# 13_RK3568_FlashSD_Controller.net
KiCad netlist of a schematic drawn in Altium Designer
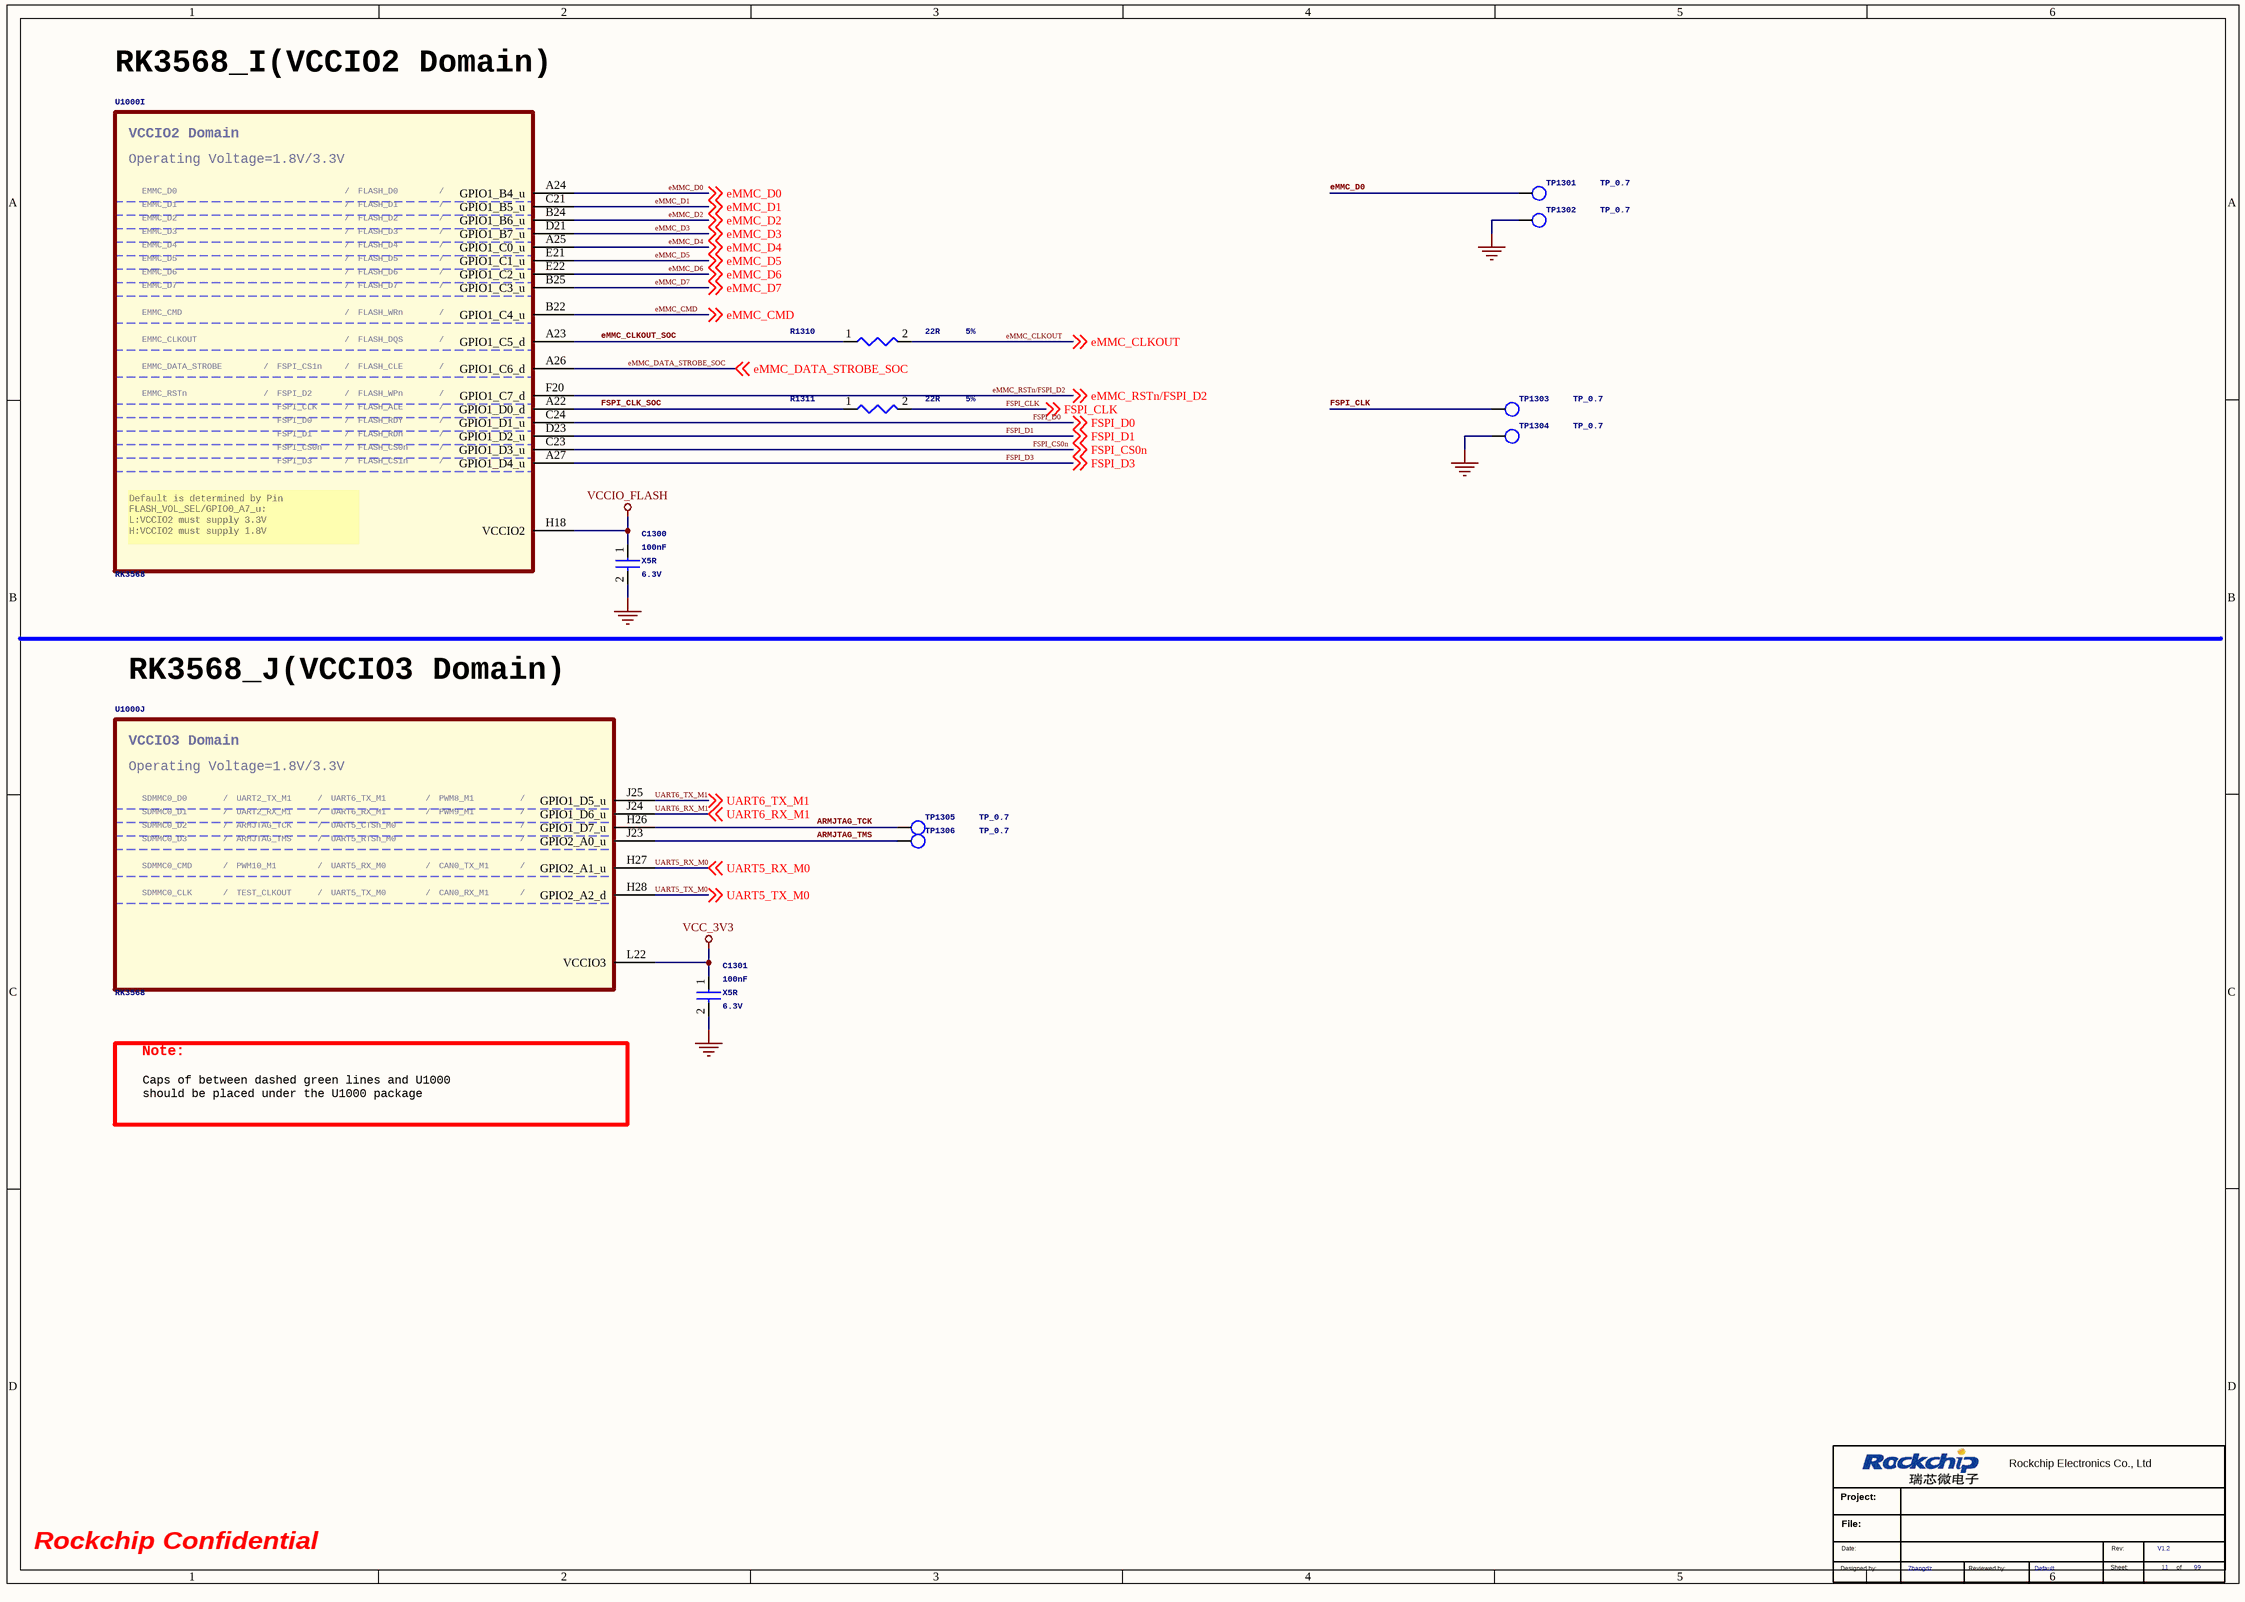
[diagram p0: 13.RK3568_FlashSD Controller.SchDoc]

(export (version "E")
  (design (tool "Eeschema 10.0.6"))
  (components
    (comp (ref "*")
      (value "Rockchip_new")
      (fields
        (field (name "SCHEMATIC PAGE COUNT") "99")
        (field (name "SCHEMATIC PAGE NUMBER") "11")
        (field (name "DESIGNER") "Zhangdz")
        (field (name "REVISION") "V1.2")
        (field (name "CHECK") "Default")
      )
      (libsource (lib "*") (part "Rockchip_new"))
    )
    (comp (ref "C1300")
      (value "100nF")
      (footprint "C0201")
      (description "cap,100.00nF,+/-10%,6.3V,X5R,C0201")
      (fields
        (field (name "VOLTAGE") "6.3V")
        (field (name "DIELECTRIC") "X5R")
        (field (name "MANUFACTURER") "TDK")
        (field (name "TOLERANCE") "10%")
        (field (name "CREATED BY") "JJJ")
      )
      (libsource (lib "*") (part "CAP NP"))
    )
    (comp (ref "C1301")
      (value "100nF")
      (footprint "C0201")
      (description "cap,100.00nF,+/-10%,6.3V,X5R,C0201")
      (fields
        (field (name "VOLTAGE") "6.3V")
        (field (name "DIELECTRIC") "X5R")
        (field (name "TOLERANCE") "10%")
        (field (name "MANUFACTURER") "TDK")
        (field (name "CREATED BY") "JJJ")
      )
      (libsource (lib "*") (part "CAP NP"))
    )
    (comp (ref "R1310")
      (value "22R")
      (footprint "R0402")
      (description "通用厚膜电阻,22R,+/-5%,R0402,1/16W.")
      (fields
        (field (name "TOLERANCE") "5%")
        (field (name "MANUFACTURER") "YAGEO")
        (field (name "CREATED BY") "YTL")
      )
      (libsource (lib "*") (part "RESISTOR"))
    )
    (comp (ref "R1311")
      (value "22R")
      (footprint "R0402")
      (description "通用厚膜电阻,22R,+/-5%,R0402,1/16W.")
      (fields
        (field (name "TOLERANCE") "5%")
        (field (name "MANUFACTURER") "YAGEO")
        (field (name "CREATED BY") "YTL")
      )
      (libsource (lib "*") (part "RESISTOR"))
    )
    (comp (ref "TP1301")
      (value "TP_0.7")
      (footprint "TP_0R70")
      (description "Test Point 0.7mm")
      (fields (field (name "CREATED BY") "JJJ"))
      (libsource (lib "*") (part "TP"))
    )
    (comp (ref "TP1302")
      (value "TP_0.7")
      (footprint "TP_0R70")
      (description "Test Point 0.7mm")
      (fields (field (name "CREATED BY") "JJJ"))
      (libsource (lib "*") (part "TP"))
    )
    (comp (ref "TP1303")
      (value "TP_0.7")
      (footprint "TP_0R70")
      (description "Test Point 0.7mm")
      (fields (field (name "CREATED BY") "JJJ"))
      (libsource (lib "*") (part "TP"))
    )
    (comp (ref "TP1304")
      (value "TP_0.7")
      (footprint "TP_0R70")
      (description "Test Point 0.7mm")
      (fields (field (name "CREATED BY") "JJJ"))
      (libsource (lib "*") (part "TP"))
    )
    (comp (ref "TP1305")
      (value "TP_0.7")
      (footprint "TP_0R70")
      (description "Test Point 0.7mm")
      (fields (field (name "CREATED BY") "JJJ"))
      (libsource (lib "*") (part "TP"))
    )
    (comp (ref "TP1306")
      (value "TP_0.7")
      (footprint "TP_0R70")
      (description "Test Point 0.7mm")
      (fields (field (name "CREATED BY") "JJJ"))
      (libsource (lib "*") (part "TP"))
    )
    (comp (ref "U1000")
      (value "RK3568")
      (footprint "BGA636_19R00X19R00X1R20")
      (description "ROCKCHIP SOC")
      (fields (field (name "MANUFACTURER") "Rockchip (瑞芯微)") (field (name "CREATED BY") "JJJ"))
      (libsource (lib "*") (part "SOC_RK3568"))
    )
  )
  (nets
    (net (code "1") (name "/ARMJTAG_TCK") (class "Default")
      (node (ref "TP1305") (pin "1") (pinfunction "1_1") (pintype "passive"))
      (node (ref "U1000") (pin "H26") (pinfunction "GPIO1_D7_u_H26") (pintype "passive"))
    )
    (net (code "2") (name "/ARMJTAG_TMS") (class "Default")
      (node (ref "TP1306") (pin "1") (pinfunction "1_1") (pintype "passive"))
      (node (ref "U1000") (pin "J23") (pinfunction "GPIO2_A0_u_J23") (pintype "passive"))
    )
    (net (code "3") (name "/FSPI_CLK_SOC") (class "Default")
      (node (ref "R1311") (pin "1") (pinfunction "1_1") (pintype "passive"))
      (node (ref "U1000") (pin "A22") (pinfunction "GPIO1_D0_d_A22") (pintype "passive"))
    )
    (net (code "4") (name "/eMMC_CLKOUT_SOC") (class "Default")
      (node (ref "R1310") (pin "1") (pinfunction "1_1") (pintype "passive"))
      (node (ref "U1000") (pin "A23") (pinfunction "GPIO1_C5_d_A23") (pintype "passive"))
    )
    (net (code "5") (name "FSPI_CLK") (class "Default")
      (node (ref "R1311") (pin "2") (pinfunction "2_2") (pintype "passive"))
      (node (ref "TP1303") (pin "1") (pinfunction "1_1") (pintype "passive"))
    )
    (net (code "6") (name "FSPI_CS0n") (class "Default")
      (node (ref "U1000") (pin "C23") (pinfunction "GPIO1_D3_u_C23") (pintype "passive"))
    )
    (net (code "7") (name "FSPI_D0") (class "Default")
      (node (ref "U1000") (pin "C24") (pinfunction "GPIO1_D1_u_C24") (pintype "passive"))
    )
    (net (code "8") (name "FSPI_D1") (class "Default")
      (node (ref "U1000") (pin "D23") (pinfunction "GPIO1_D2_u_D23") (pintype "passive"))
    )
    (net (code "9") (name "FSPI_D3") (class "Default")
      (node (ref "U1000") (pin "A27") (pinfunction "GPIO1_D4_u_A27") (pintype "passive"))
    )
    (net (code "10") (name "GND") (class "Default")
      (node (ref "C1300") (pin "2") (pinfunction "2_2") (pintype "passive"))
      (node (ref "C1301") (pin "2") (pinfunction "2_2") (pintype "passive"))
      (node (ref "TP1302") (pin "1") (pinfunction "1_1") (pintype "passive"))
      (node (ref "TP1304") (pin "1") (pinfunction "1_1") (pintype "passive"))
    )
    (net (code "11") (name "UART5_RX_M0") (class "Default")
      (node (ref "U1000") (pin "H27") (pinfunction "GPIO2_A1_u_H27") (pintype "passive"))
    )
    (net (code "12") (name "UART5_TX_M0") (class "Default")
      (node (ref "U1000") (pin "H28") (pinfunction "GPIO2_A2_d_H28") (pintype "passive"))
    )
    (net (code "13") (name "UART6_RX_M1") (class "Default")
      (node (ref "U1000") (pin "J24") (pinfunction "GPIO1_D6_u_J24") (pintype "passive"))
    )
    (net (code "14") (name "UART6_TX_M1") (class "Default")
      (node (ref "U1000") (pin "J25") (pinfunction "GPIO1_D5_u_J25") (pintype "passive"))
    )
    (net (code "15") (name "VCCIO_FLASH") (class "Default")
      (node (ref "C1300") (pin "1") (pinfunction "1_1") (pintype "passive"))
      (node (ref "U1000") (pin "H18") (pinfunction "VCCIO2_H18") (pintype "passive"))
    )
    (net (code "16") (name "VCC_3V3") (class "Default")
      (node (ref "C1301") (pin "1") (pinfunction "1_1") (pintype "passive"))
      (node (ref "U1000") (pin "L22") (pinfunction "VCCIO3_L22") (pintype "passive"))
    )
    (net (code "17") (name "eMMC_CLKOUT") (class "Default")
      (node (ref "R1310") (pin "2") (pinfunction "2_2") (pintype "passive"))
    )
    (net (code "18") (name "eMMC_CMD") (class "Default")
      (node (ref "U1000") (pin "B22") (pinfunction "GPIO1_C4_u_B22") (pintype "passive"))
    )
    (net (code "19") (name "eMMC_D0") (class "Default")
      (node (ref "TP1301") (pin "1") (pinfunction "1_1") (pintype "passive"))
      (node (ref "U1000") (pin "A24") (pinfunction "GPIO1_B4_u_A24") (pintype "passive"))
    )
    (net (code "20") (name "eMMC_D1") (class "Default")
      (node (ref "U1000") (pin "C21") (pinfunction "GPIO1_B5_u_C21") (pintype "passive"))
    )
    (net (code "21") (name "eMMC_D2") (class "Default")
      (node (ref "U1000") (pin "B24") (pinfunction "GPIO1_B6_u_B24") (pintype "passive"))
    )
    (net (code "22") (name "eMMC_D3") (class "Default")
      (node (ref "U1000") (pin "D21") (pinfunction "GPIO1_B7_u_D21") (pintype "passive"))
    )
    (net (code "23") (name "eMMC_D4") (class "Default")
      (node (ref "U1000") (pin "A25") (pinfunction "GPIO1_C0_u_A25") (pintype "passive"))
    )
    (net (code "24") (name "eMMC_D5") (class "Default")
      (node (ref "U1000") (pin "E21") (pinfunction "GPIO1_C1_u_E21") (pintype "passive"))
    )
    (net (code "25") (name "eMMC_D6") (class "Default")
      (node (ref "U1000") (pin "E22") (pinfunction "GPIO1_C2_u_E22") (pintype "passive"))
    )
    (net (code "26") (name "eMMC_D7") (class "Default")
      (node (ref "U1000") (pin "B25") (pinfunction "GPIO1_C3_u_B25") (pintype "passive"))
    )
    (net (code "27") (name "eMMC_DATA_STROBE_SOC") (class "Default")
      (node (ref "U1000") (pin "A26") (pinfunction "GPIO1_C6_d_A26") (pintype "passive"))
    )
    (net (code "28") (name "eMMC_RSTn{slash}FSPI_D2") (class "Default")
      (node (ref "U1000") (pin "F20") (pinfunction "GPIO1_C7_d_F20") (pintype "passive"))
    )
  )
)
